# strombegrenzung_pnp.net
KiCad netlist of a schematic drawn in EAGLE
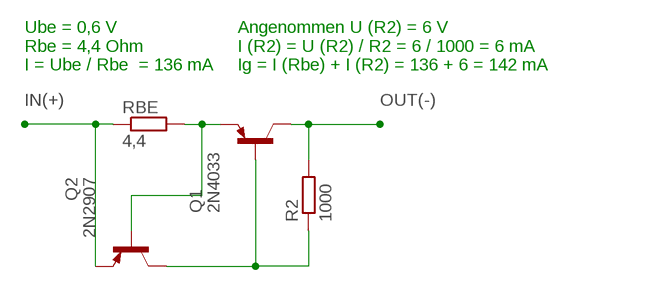
[diagram p0: schematic, sheet 1]

(export (version "E")
  (design (tool "Eeschema 10.0.6"))
  (components
    (comp (ref "Q1")
      (value "2N4033")
      (footprint "eagle-import:TO39")
      (fields (field (name "SPICEPREFIX") "Q"))
      (libsource (lib "eagle-import") (part "2N4033"))
    )
    (comp (ref "Q2")
      (value "2N2907")
      (footprint "eagle-import:TO18")
      (libsource (lib "eagle-import") (part "2N2907"))
    )
    (comp (ref "R2")
      (value "1000")
      (footprint "eagle-import:0207_10")
      (libsource (lib "eagle-import") (part "R-EU_0207/10"))
    )
    (comp (ref "RBE")
      (value "4,4")
      (footprint "eagle-import:0207_7")
      (libsource (lib "eagle-import") (part "R-EU_0207/7"))
    )
  )
  (nets
    (net (code "1") (name "/IN(+)") (class "Default")
      (node (ref "Q2") (pin "1") (pinfunction "E_1") (pintype "passive"))
      (node (ref "RBE") (pin "1") (pinfunction "1_1") (pintype "passive"))
    )
    (net (code "2") (name "/OUT(-)") (class "Default")
      (node (ref "Q1") (pin "3") (pinfunction "C_3") (pintype "passive"))
      (node (ref "R2") (pin "2") (pinfunction "2_2") (pintype "passive"))
    )
    (net (code "3") (name "Net-(Q1-B)") (class "Default")
      (node (ref "Q1") (pin "2") (pinfunction "B_2") (pintype "passive"))
      (node (ref "Q2") (pin "3") (pinfunction "C_3") (pintype "passive"))
      (node (ref "R2") (pin "1") (pinfunction "1_1") (pintype "passive"))
    )
    (net (code "4") (name "Net-(Q1-E)") (class "Default")
      (node (ref "Q1") (pin "1") (pinfunction "E_1") (pintype "passive"))
      (node (ref "Q2") (pin "2") (pinfunction "B_2") (pintype "passive"))
      (node (ref "RBE") (pin "2") (pinfunction "2_2") (pintype "passive"))
    )
  )
)
